# InterfaceExtension.net
KiCad netlist of a schematic drawn in Altium Designer
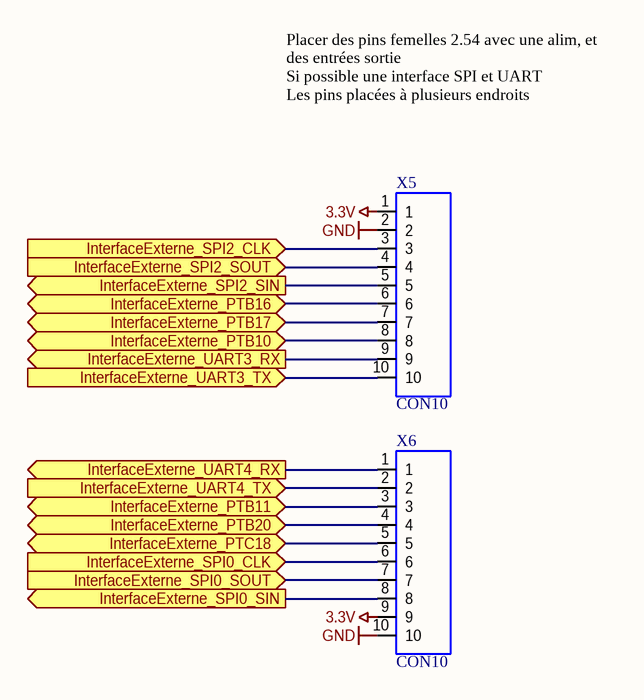
[diagram p0: InterfaceExtension.SchDoc]

(export (version "E")
  (design (tool "Eeschema 10.0.6"))
  (components
    (comp (ref "X5") (value "CON10") (footprint "SIP10") (libsource (lib "EISI") (part "CON10")))
    (comp (ref "X6") (value "CON10") (footprint "SIP10") (libsource (lib "EISI") (part "CON10")))
  )
  (nets
    (net (code "1") (name "/InterfaceExterne_PTB10") (class "Default")
      (node (ref "X5") (pin "8") (pinfunction "8_8") (pintype "passive"))
    )
    (net (code "2") (name "/InterfaceExterne_PTB11") (class "Default")
      (node (ref "X6") (pin "3") (pinfunction "3_3") (pintype "passive"))
    )
    (net (code "3") (name "/InterfaceExterne_PTB16") (class "Default")
      (node (ref "X5") (pin "6") (pinfunction "6_6") (pintype "passive"))
    )
    (net (code "4") (name "/InterfaceExterne_PTB17") (class "Default")
      (node (ref "X5") (pin "7") (pinfunction "7_7") (pintype "passive"))
    )
    (net (code "5") (name "/InterfaceExterne_PTB20") (class "Default")
      (node (ref "X6") (pin "4") (pinfunction "4_4") (pintype "passive"))
    )
    (net (code "6") (name "/InterfaceExterne_PTC18") (class "Default")
      (node (ref "X6") (pin "5") (pinfunction "5_5") (pintype "passive"))
    )
    (net (code "7") (name "/InterfaceExterne_SPI0_CLK") (class "Default")
      (node (ref "X6") (pin "6") (pinfunction "6_6") (pintype "passive"))
    )
    (net (code "8") (name "/InterfaceExterne_SPI0_SIN") (class "Default")
      (node (ref "X6") (pin "8") (pinfunction "8_8") (pintype "passive"))
    )
    (net (code "9") (name "/InterfaceExterne_SPI0_SOUT") (class "Default")
      (node (ref "X6") (pin "7") (pinfunction "7_7") (pintype "passive"))
    )
    (net (code "10") (name "/InterfaceExterne_SPI2_CLK") (class "Default")
      (node (ref "X5") (pin "3") (pinfunction "3_3") (pintype "passive"))
    )
    (net (code "11") (name "/InterfaceExterne_SPI2_SIN") (class "Default")
      (node (ref "X5") (pin "5") (pinfunction "5_5") (pintype "passive"))
    )
    (net (code "12") (name "/InterfaceExterne_SPI2_SOUT") (class "Default")
      (node (ref "X5") (pin "4") (pinfunction "4_4") (pintype "passive"))
    )
    (net (code "13") (name "/InterfaceExterne_UART3_RX") (class "Default")
      (node (ref "X5") (pin "9") (pinfunction "9_9") (pintype "passive"))
    )
    (net (code "14") (name "/InterfaceExterne_UART3_TX") (class "Default")
      (node (ref "X5") (pin "10") (pinfunction "10_10") (pintype "passive"))
    )
    (net (code "15") (name "/InterfaceExterne_UART4_RX") (class "Default")
      (node (ref "X6") (pin "1") (pinfunction "1_1") (pintype "passive"))
    )
    (net (code "16") (name "/InterfaceExterne_UART4_TX") (class "Default")
      (node (ref "X6") (pin "2") (pinfunction "2_2") (pintype "passive"))
    )
    (net (code "17") (name "3.3V") (class "Default")
      (node (ref "X5") (pin "1") (pinfunction "1_1") (pintype "passive"))
      (node (ref "X6") (pin "9") (pinfunction "9_9") (pintype "passive"))
    )
    (net (code "18") (name "GND") (class "Default")
      (node (ref "X5") (pin "2") (pinfunction "2_2") (pintype "passive"))
      (node (ref "X6") (pin "10") (pinfunction "10_10") (pintype "passive"))
    )
  )
)
